# mute_control.net
KiCad netlist of a schematic drawn in EAGLE
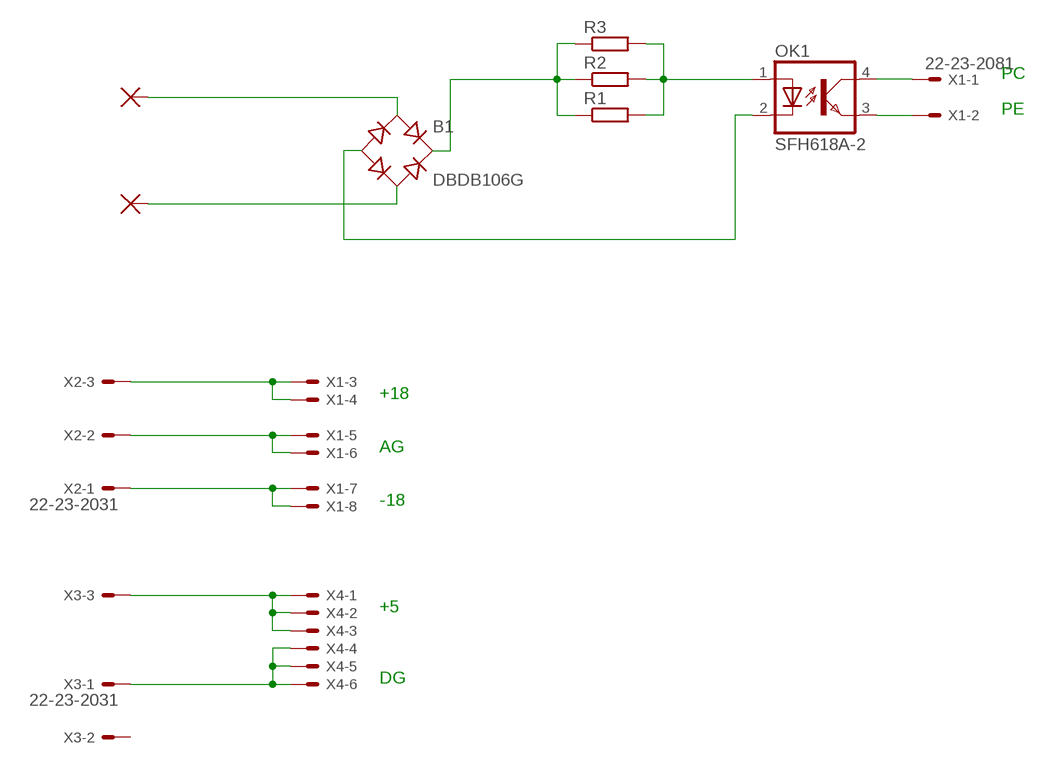
[diagram p0: schematic, sheet 1]

(export (version "E")
  (design (tool "Eeschema 10.0.6"))
  (components
    (comp (ref "AC")
      (value "3,17/1,3")
      (footprint "eagle-import:OBLONG")
      (libsource (lib "eagle-import") (part "3,17/1,3"))
    )
    (comp (ref "B1")
      (value "DBDB106G")
      (footprint "eagle-import:DB")
      (libsource (lib "eagle-import") (part "DB?GDB106"))
    )
    (comp (ref "OK1")
      (value "SFH618A-2")
      (footprint "eagle-import:DIP4")
      (fields (field (name "MF") "VISHAY/TELEFUNKEN"))
      (libsource (lib "eagle-import") (part "SFH618?A-2"))
    )
    (comp (ref "PAD1")
      (value "3,17/1,3")
      (footprint "eagle-import:OBLONG")
      (libsource (lib "eagle-import") (part "3,17/1,3"))
    )
    (comp (ref "R1")
      (value "R-EU_0817/22")
      (footprint "eagle-import:P0817_22")
      (libsource (lib "eagle-import") (part "R-EU_0817/22"))
    )
    (comp (ref "R2")
      (value "R-EU_0817/22")
      (footprint "eagle-import:P0817_22")
      (libsource (lib "eagle-import") (part "R-EU_0817/22"))
    )
    (comp (ref "R3")
      (value "R-EU_0817/22")
      (footprint "eagle-import:P0817_22")
      (libsource (lib "eagle-import") (part "R-EU_0817/22"))
    )
    (comp (ref "X1")
      (value "22-23-2081")
      (footprint "eagle-import:22-23-2081")
      (fields (field (name "MF") "MOLEX"))
      (libsource (lib "eagle-import") (part "22-23-2081"))
    )
    (comp (ref "X2")
      (value "22-23-2031")
      (footprint "eagle-import:22-23-2031")
      (fields (field (name "MF") "MOLEX"))
      (libsource (lib "eagle-import") (part "22-23-2031"))
    )
    (comp (ref "X3")
      (value "22-23-2031")
      (footprint "eagle-import:22-23-2031")
      (fields (field (name "MF") "MOLEX"))
      (libsource (lib "eagle-import") (part "22-23-2031"))
    )
    (comp (ref "X4")
      (value "22-23-2061")
      (footprint "eagle-import:22-23-2061")
      (fields (field (name "MF") "MOLEX"))
      (libsource (lib "eagle-import") (part "22-23-2061"))
    )
  )
  (nets
    (net (code "1") (name "Net-(AC-P)") (class "Default")
      (node (ref "AC") (pin "P$1") (pinfunction "P_P$1") (pintype "passive"))
      (node (ref "B1") (pin "AC2") (pinfunction "AC2_AC2") (pintype "passive"))
    )
    (net (code "2") (name "Net-(B1-Pad+)") (class "Default")
      (node (ref "B1") (pin "+") (pinfunction "+_+") (pintype "passive"))
      (node (ref "R1") (pin "1") (pinfunction "1_1") (pintype "passive"))
      (node (ref "R2") (pin "1") (pinfunction "1_1") (pintype "passive"))
      (node (ref "R3") (pin "1") (pinfunction "1_1") (pintype "passive"))
    )
    (net (code "3") (name "Net-(OK1-A)") (class "Default")
      (node (ref "OK1") (pin "1") (pinfunction "A_1") (pintype "passive"))
      (node (ref "R1") (pin "2") (pinfunction "2_2") (pintype "passive"))
      (node (ref "R2") (pin "2") (pinfunction "2_2") (pintype "passive"))
      (node (ref "R3") (pin "2") (pinfunction "2_2") (pintype "passive"))
    )
    (net (code "4") (name "Net-(OK1-C)") (class "Default")
      (node (ref "B1") (pin "-") (pinfunction "-_-") (pintype "passive"))
      (node (ref "OK1") (pin "2") (pinfunction "C_2") (pintype "passive"))
    )
    (net (code "5") (name "Net-(OK1-COL)") (class "Default")
      (node (ref "OK1") (pin "4") (pinfunction "COL_4") (pintype "passive"))
      (node (ref "X1") (pin "1") (pinfunction "S_1") (pintype "passive"))
    )
    (net (code "6") (name "Net-(OK1-EMIT)") (class "Default")
      (node (ref "OK1") (pin "3") (pinfunction "EMIT_3") (pintype "passive"))
      (node (ref "X1") (pin "2") (pinfunction "S_2") (pintype "passive"))
    )
    (net (code "7") (name "Net-(PAD1-P)") (class "Default")
      (node (ref "B1") (pin "AC1") (pinfunction "AC1_AC1") (pintype "passive"))
      (node (ref "PAD1") (pin "P$1") (pinfunction "P_P$1") (pintype "passive"))
    )
    (net (code "8") (name "Net-(X1C-S)") (class "Default")
      (node (ref "X1") (pin "3") (pinfunction "S_3") (pintype "passive"))
      (node (ref "X1") (pin "4") (pinfunction "S_4") (pintype "passive"))
      (node (ref "X2") (pin "3") (pinfunction "S_3") (pintype "passive"))
    )
    (net (code "9") (name "Net-(X1E-S)") (class "Default")
      (node (ref "X1") (pin "5") (pinfunction "S_5") (pintype "passive"))
      (node (ref "X1") (pin "6") (pinfunction "S_6") (pintype "passive"))
      (node (ref "X2") (pin "2") (pinfunction "S_2") (pintype "passive"))
    )
    (net (code "10") (name "Net-(X1G-S)") (class "Default")
      (node (ref "X1") (pin "7") (pinfunction "S_7") (pintype "passive"))
      (node (ref "X1") (pin "8") (pinfunction "S_8") (pintype "passive"))
      (node (ref "X2") (pin "1") (pinfunction "S_1") (pintype "passive"))
    )
    (net (code "11") (name "Net-(X3A-S)") (class "Default")
      (node (ref "X3") (pin "1") (pinfunction "S_1") (pintype "passive"))
      (node (ref "X4") (pin "4") (pinfunction "S_4") (pintype "passive"))
      (node (ref "X4") (pin "5") (pinfunction "S_5") (pintype "passive"))
      (node (ref "X4") (pin "6") (pinfunction "S_6") (pintype "passive"))
    )
    (net (code "12") (name "Net-(X3C-S)") (class "Default")
      (node (ref "X3") (pin "3") (pinfunction "S_3") (pintype "passive"))
      (node (ref "X4") (pin "1") (pinfunction "S_1") (pintype "passive"))
      (node (ref "X4") (pin "2") (pinfunction "S_2") (pintype "passive"))
      (node (ref "X4") (pin "3") (pinfunction "S_3") (pintype "passive"))
    )
    (net (code "13") (name "unconnected-(X3B-S-Pad2)") (class "Default")
      (node (ref "X3") (pin "2") (pinfunction "S_2") (pintype "passive"))
    )
  )
)
